# DAC.net
KiCad netlist of a schematic drawn in EAGLE
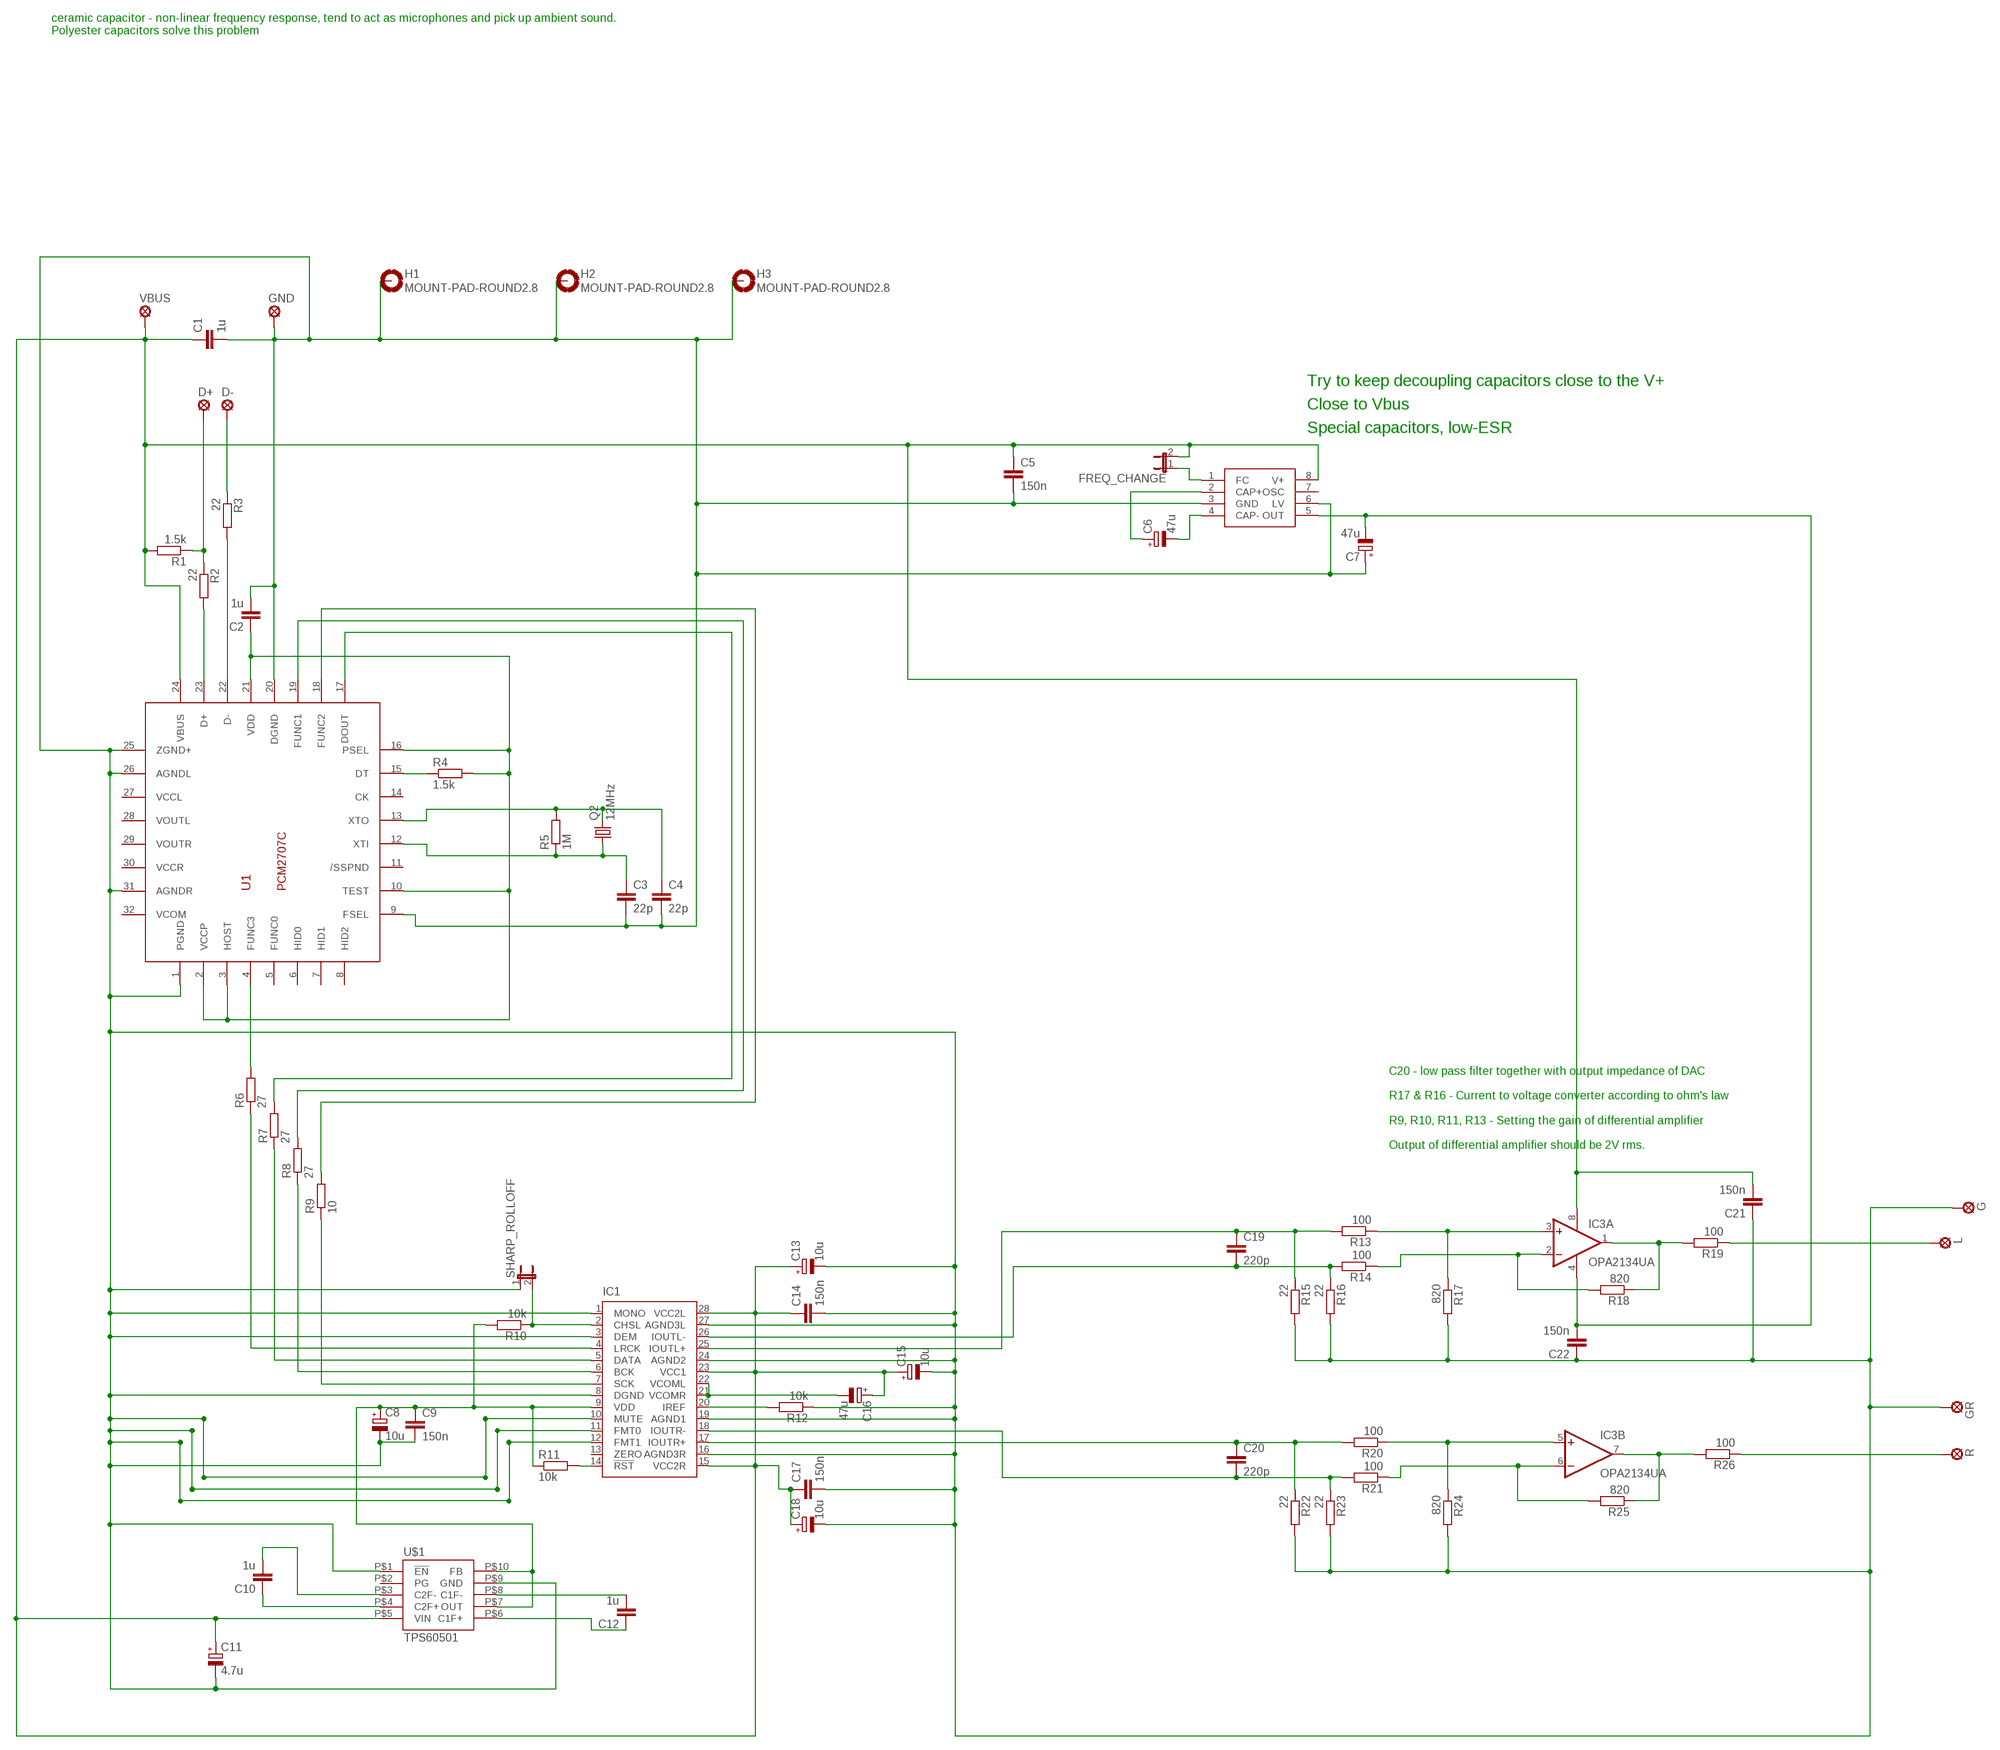
[diagram p0: schematic, sheet 1]

(export (version "E")
  (design (tool "Eeschema 10.0.6"))
  (components
    (comp (ref "C1")
      (value "1u")
      (footprint "eagle-import:C050-050X075")
      (libsource (lib "eagle-import") (part "C-EU050-050X075"))
    )
    (comp (ref "C2")
      (value "1u")
      (footprint "eagle-import:C050-050X075")
      (libsource (lib "eagle-import") (part "C-EU050-050X075"))
    )
    (comp (ref "C3")
      (value "22p")
      (footprint "eagle-import:C0603")
      (libsource (lib "eagle-import") (part "C-EUC0603"))
    )
    (comp (ref "C4")
      (value "22p")
      (footprint "eagle-import:C0603")
      (libsource (lib "eagle-import") (part "C-EUC0603"))
    )
    (comp (ref "C5")
      (value "150n")
      (footprint "eagle-import:C050-025X075")
      (libsource (lib "eagle-import") (part "C-EU050-025X075"))
    )
    (comp (ref "C6")
      (value "47u")
      (footprint "eagle-import:PANASONIC_D")
      (libsource (lib "eagle-import") (part "CPOL-EUD"))
    )
    (comp (ref "C7")
      (value "47u")
      (footprint "eagle-import:PANASONIC_D")
      (libsource (lib "eagle-import") (part "CPOL-EUD"))
    )
    (comp (ref "C8")
      (value "10u")
      (footprint "eagle-import:153CLV-0405")
      (libsource (lib "eagle-import") (part "CPOL-EU153CLV-0405"))
    )
    (comp (ref "C9")
      (value "150n")
      (footprint "eagle-import:C050-025X075")
      (libsource (lib "eagle-import") (part "C-EU050-025X075"))
    )
    (comp (ref "C10")
      (value "1u")
      (footprint "eagle-import:C050-050X075")
      (libsource (lib "eagle-import") (part "C-EU050-050X075"))
    )
    (comp (ref "C11")
      (value "4.7u")
      (footprint "eagle-import:E2-5")
      (libsource (lib "eagle-import") (part "CPOL-EUE2-5"))
    )
    (comp (ref "C12")
      (value "1u")
      (footprint "eagle-import:C050-050X075")
      (libsource (lib "eagle-import") (part "C-EU050-050X075"))
    )
    (comp (ref "C13")
      (value "10u")
      (footprint "eagle-import:E2-5")
      (libsource (lib "eagle-import") (part "CPOL-EUE2-5"))
    )
    (comp (ref "C14")
      (value "150n")
      (footprint "eagle-import:C050-025X075")
      (libsource (lib "eagle-import") (part "C-EU050-025X075"))
    )
    (comp (ref "C15")
      (value "10u")
      (footprint "eagle-import:E2-5")
      (libsource (lib "eagle-import") (part "CPOL-EUE2-5"))
    )
    (comp (ref "C16")
      (value "47u")
      (footprint "eagle-import:E2-5")
      (libsource (lib "eagle-import") (part "CPOL-EUE2-5"))
    )
    (comp (ref "C17")
      (value "150n")
      (footprint "eagle-import:C050-025X075")
      (libsource (lib "eagle-import") (part "C-EU050-025X075"))
    )
    (comp (ref "C18")
      (value "10u")
      (footprint "eagle-import:E2-5")
      (libsource (lib "eagle-import") (part "CPOL-EUE2-5"))
    )
    (comp (ref "C19")
      (value "220p")
      (footprint "eagle-import:C025-024X044")
      (libsource (lib "eagle-import") (part "C-EU025-024X044"))
    )
    (comp (ref "C20")
      (value "220p")
      (footprint "eagle-import:C025-024X044")
      (libsource (lib "eagle-import") (part "C-EU025-024X044"))
    )
    (comp (ref "C21")
      (value "150n")
      (footprint "eagle-import:C050-025X075")
      (libsource (lib "eagle-import") (part "C-EU050-025X075"))
    )
    (comp (ref "C22")
      (value "150n")
      (footprint "eagle-import:C050-025X075")
      (libsource (lib "eagle-import") (part "C-EU050-025X075"))
    )
    (comp (ref "D+")
      (value "LSP10")
      (footprint "eagle-import:LSP10")
      (libsource (lib "eagle-import") (part "LSP10"))
    )
    (comp (ref "D-")
      (value "LSP10")
      (footprint "eagle-import:LSP10")
      (libsource (lib "eagle-import") (part "LSP10"))
    )
    (comp (ref "FREQ_CHANGE")
      (value "JP1E")
      (footprint "eagle-import:JP1")
      (libsource (lib "eagle-import") (part "JP1E"))
    )
    (comp (ref "G")
      (value "LSP10")
      (footprint "eagle-import:LSP10")
      (libsource (lib "eagle-import") (part "LSP10"))
    )
    (comp (ref "GND")
      (value "LSP10")
      (footprint "eagle-import:LSP10")
      (libsource (lib "eagle-import") (part "LSP10"))
    )
    (comp (ref "GR")
      (value "LSP10")
      (footprint "eagle-import:LSP10")
      (libsource (lib "eagle-import") (part "LSP10"))
    )
    (comp (ref "H1")
      (value "MOUNT-PAD-ROUND2.8")
      (footprint "eagle-import:2,8-PAD")
      (libsource (lib "eagle-import") (part "MOUNT-PAD-ROUND2.8"))
    )
    (comp (ref "H2")
      (value "MOUNT-PAD-ROUND2.8")
      (footprint "eagle-import:2,8-PAD")
      (libsource (lib "eagle-import") (part "MOUNT-PAD-ROUND2.8"))
    )
    (comp (ref "H3")
      (value "MOUNT-PAD-ROUND2.8")
      (footprint "eagle-import:2,8-PAD")
      (libsource (lib "eagle-import") (part "MOUNT-PAD-ROUND2.8"))
    )
    (comp (ref "IC1")
      (value "PCM1794A")
      (footprint "eagle-import:SSOP28DB")
      (libsource (lib "eagle-import") (part "PCM1794A"))
    )
    (comp (ref "IC3")
      (value "OPA2134UA")
      (footprint "eagle-import:SO08")
      (libsource (lib "eagle-import") (part "OPA2UA134"))
    )
    (comp (ref "L")
      (value "LSP10")
      (footprint "eagle-import:LSP10")
      (libsource (lib "eagle-import") (part "LSP10"))
    )
    (comp (ref "Q2")
      (value "12MHz")
      (footprint "eagle-import:HC49_S")
      (libsource (lib "eagle-import") (part "CRYSTALHC49S"))
    )
    (comp (ref "R")
      (value "LSP10")
      (footprint "eagle-import:LSP10")
      (libsource (lib "eagle-import") (part "LSP10"))
    )
    (comp (ref "R1")
      (value "1.5k")
      (footprint "eagle-import:R0603")
      (libsource (lib "eagle-import") (part "R-EU_R0603"))
    )
    (comp (ref "R2")
      (value "22")
      (footprint "eagle-import:R0603")
      (libsource (lib "eagle-import") (part "R-EU_R0603"))
    )
    (comp (ref "R3")
      (value "22")
      (footprint "eagle-import:R0603")
      (libsource (lib "eagle-import") (part "R-EU_R0603"))
    )
    (comp (ref "R4")
      (value "1.5k")
      (footprint "eagle-import:R0603")
      (libsource (lib "eagle-import") (part "R-EU_R0603"))
    )
    (comp (ref "R5")
      (value "1M")
      (footprint "eagle-import:R0603")
      (libsource (lib "eagle-import") (part "R-EU_R0603"))
    )
    (comp (ref "R6")
      (value "27")
      (footprint "eagle-import:R0603")
      (libsource (lib "eagle-import") (part "R-EU_R0603"))
    )
    (comp (ref "R7")
      (value "27")
      (footprint "eagle-import:R0603")
      (libsource (lib "eagle-import") (part "R-EU_R0603"))
    )
    (comp (ref "R8")
      (value "27")
      (footprint "eagle-import:R0603")
      (libsource (lib "eagle-import") (part "R-EU_R0603"))
    )
    (comp (ref "R9")
      (value "10")
      (footprint "eagle-import:R0603")
      (libsource (lib "eagle-import") (part "R-EU_R0603"))
    )
    (comp (ref "R10")
      (value "10k")
      (footprint "eagle-import:R0603")
      (libsource (lib "eagle-import") (part "R-EU_R0603"))
    )
    (comp (ref "R11")
      (value "10k")
      (footprint "eagle-import:R0603")
      (libsource (lib "eagle-import") (part "R-EU_R0603"))
    )
    (comp (ref "R12")
      (value "10k")
      (footprint "eagle-import:0207_10")
      (libsource (lib "eagle-import") (part "R-EU_0207/10"))
    )
    (comp (ref "R13")
      (value "100")
      (footprint "eagle-import:0207_10")
      (libsource (lib "eagle-import") (part "R-EU_0207/10"))
    )
    (comp (ref "R14")
      (value "100")
      (footprint "eagle-import:0207_10")
      (libsource (lib "eagle-import") (part "R-EU_0207/10"))
    )
    (comp (ref "R15")
      (value "22")
      (footprint "eagle-import:0207_10")
      (libsource (lib "eagle-import") (part "R-EU_0207/10"))
    )
    (comp (ref "R16")
      (value "22")
      (footprint "eagle-import:0207_10")
      (libsource (lib "eagle-import") (part "R-EU_0207/10"))
    )
    (comp (ref "R17")
      (value "820")
      (footprint "eagle-import:0207_10")
      (libsource (lib "eagle-import") (part "R-EU_0207/10"))
    )
    (comp (ref "R18")
      (value "820")
      (footprint "eagle-import:0207_10")
      (libsource (lib "eagle-import") (part "R-EU_0207/10"))
    )
    (comp (ref "R19")
      (value "100")
      (footprint "eagle-import:0207_10")
      (libsource (lib "eagle-import") (part "R-EU_0207/10"))
    )
    (comp (ref "R20")
      (value "100")
      (footprint "eagle-import:0207_10")
      (libsource (lib "eagle-import") (part "R-EU_0207/10"))
    )
    (comp (ref "R21")
      (value "100")
      (footprint "eagle-import:0207_10")
      (libsource (lib "eagle-import") (part "R-EU_0207/10"))
    )
    (comp (ref "R22")
      (value "22")
      (footprint "eagle-import:0207_10")
      (libsource (lib "eagle-import") (part "R-EU_0207/10"))
    )
    (comp (ref "R23")
      (value "22")
      (footprint "eagle-import:0207_10")
      (libsource (lib "eagle-import") (part "R-EU_0207/10"))
    )
    (comp (ref "R24")
      (value "820")
      (footprint "eagle-import:0207_10")
      (libsource (lib "eagle-import") (part "R-EU_0207/10"))
    )
    (comp (ref "R25")
      (value "820")
      (footprint "eagle-import:0207_10")
      (libsource (lib "eagle-import") (part "R-EU_0207/10"))
    )
    (comp (ref "R26")
      (value "100")
      (footprint "eagle-import:0207_10")
      (libsource (lib "eagle-import") (part "R-EU_0207/10"))
    )
    (comp (ref "SHARP_ROLLOFF")
      (value "JP1E")
      (footprint "eagle-import:JP1")
      (libsource (lib "eagle-import") (part "JP1E"))
    )
    (comp (ref "U$1")
      (value "TPS60501")
      (footprint "eagle-import:VSSOP10")
      (libsource (lib "eagle-import") (part "TPS60501"))
    )
    (comp (ref "U$2")
      (value "LM2662")
      (footprint "eagle-import:SOIC8")
      (libsource (lib "eagle-import") (part "LM2662"))
    )
    (comp (ref "U1")
      (value "PCM2707C")
      (footprint "eagle-import:32TQFP_PCM2707C")
      (libsource (lib "eagle-import") (part "PCM2707C_TQFP32{dblquote}"))
    )
    (comp (ref "VBUS")
      (value "LSP10")
      (footprint "eagle-import:LSP10")
      (libsource (lib "eagle-import") (part "LSP10"))
    )
  )
  (nets
    (net (code "1") (name "Net-(D+-PadMP)") (class "Default")
      (node (ref "D+") (pin "MP") (pinfunction "MP_MP") (pintype "passive"))
      (node (ref "R1") (pin "1") (pinfunction "1_1") (pintype "passive"))
      (node (ref "R2") (pin "1") (pinfunction "1_1") (pintype "passive"))
    )
    (net (code "2") (name "Net-(D--PadMP)") (class "Default")
      (node (ref "D-") (pin "MP") (pinfunction "MP_MP") (pintype "passive"))
      (node (ref "R3") (pin "1") (pinfunction "1_1") (pintype "passive"))
    )
    (net (code "3") (name "Net-(H1-MOUNT)") (class "Default")
      (node (ref "C1") (pin "2") (pinfunction "2_2") (pintype "passive"))
      (node (ref "C11") (pin "-") (pinfunction "-_-") (pintype "passive"))
      (node (ref "C13") (pin "-") (pinfunction "-_-") (pintype "passive"))
      (node (ref "C14") (pin "2") (pinfunction "2_2") (pintype "passive"))
      (node (ref "C15") (pin "-") (pinfunction "-_-") (pintype "passive"))
      (node (ref "C17") (pin "2") (pinfunction "2_2") (pintype "passive"))
      (node (ref "C18") (pin "-") (pinfunction "-_-") (pintype "passive"))
      (node (ref "C2") (pin "2") (pinfunction "2_2") (pintype "passive"))
      (node (ref "C21") (pin "1") (pinfunction "1_1") (pintype "passive"))
      (node (ref "C22") (pin "1") (pinfunction "1_1") (pintype "passive"))
      (node (ref "C3") (pin "2") (pinfunction "2_2") (pintype "passive"))
      (node (ref "C4") (pin "2") (pinfunction "2_2") (pintype "passive"))
      (node (ref "C5") (pin "2") (pinfunction "2_2") (pintype "passive"))
      (node (ref "C7") (pin "+") (pinfunction "+_+") (pintype "passive"))
      (node (ref "C8") (pin "-") (pinfunction "-_-") (pintype "passive"))
      (node (ref "C9") (pin "2") (pinfunction "2_2") (pintype "passive"))
      (node (ref "G") (pin "MP") (pinfunction "MP_MP") (pintype "passive"))
      (node (ref "GND") (pin "MP") (pinfunction "MP_MP") (pintype "passive"))
      (node (ref "GR") (pin "MP") (pinfunction "MP_MP") (pintype "passive"))
      (node (ref "H1") (pin "B2,8") (pinfunction "MOUNT_B2,8") (pintype "passive"))
      (node (ref "H2") (pin "B2,8") (pinfunction "MOUNT_B2,8") (pintype "passive"))
      (node (ref "H3") (pin "B2,8") (pinfunction "MOUNT_B2,8") (pintype "passive"))
      (node (ref "IC1") (pin "1") (pinfunction "MONO_1") (pintype "input"))
      (node (ref "IC1") (pin "10") (pinfunction "MUTE_10") (pintype "input"))
      (node (ref "IC1") (pin "11") (pinfunction "FMT0_11") (pintype "input"))
      (node (ref "IC1") (pin "12") (pinfunction "FMT1_12") (pintype "input"))
      (node (ref "IC1") (pin "16") (pinfunction "AGND3R_16") (pintype "power_in"))
      (node (ref "IC1") (pin "19") (pinfunction "AGND1_19") (pintype "power_in"))
      (node (ref "IC1") (pin "24") (pinfunction "AGND2_24") (pintype "power_in"))
      (node (ref "IC1") (pin "27") (pinfunction "AGND3L_27") (pintype "power_in"))
      (node (ref "IC1") (pin "3") (pinfunction "DEM_3") (pintype "input"))
      (node (ref "IC1") (pin "8") (pinfunction "DGND_8") (pintype "power_in"))
      (node (ref "R12") (pin "1") (pinfunction "1_1") (pintype "passive"))
      (node (ref "R15") (pin "2") (pinfunction "2_2") (pintype "passive"))
      (node (ref "R16") (pin "2") (pinfunction "2_2") (pintype "passive"))
      (node (ref "R17") (pin "2") (pinfunction "2_2") (pintype "passive"))
      (node (ref "R22") (pin "2") (pinfunction "2_2") (pintype "passive"))
      (node (ref "R23") (pin "2") (pinfunction "2_2") (pintype "passive"))
      (node (ref "R24") (pin "2") (pinfunction "2_2") (pintype "passive"))
      (node (ref "SHARP_ROLLOFF") (pin "1") (pinfunction "1_1") (pintype "passive"))
      (node (ref "U$1") (pin "P$1") (pinfunction "~{EN}_P$1") (pintype "bidirectional"))
      (node (ref "U$1") (pin "P$9") (pinfunction "GND_P$9") (pintype "bidirectional"))
      (node (ref "U$2") (pin "3") (pinfunction "GND_3") (pintype "bidirectional"))
      (node (ref "U$2") (pin "6") (pinfunction "LV_6") (pintype "bidirectional"))
      (node (ref "U1") (pin "1") (pinfunction "PGND_1") (pintype "bidirectional"))
      (node (ref "U1") (pin "20") (pinfunction "DGND_20") (pintype "bidirectional"))
      (node (ref "U1") (pin "25") (pinfunction "ZGND+_25") (pintype "bidirectional"))
      (node (ref "U1") (pin "26") (pinfunction "AGNDL_26") (pintype "bidirectional"))
      (node (ref "U1") (pin "31") (pinfunction "AGNDR_31") (pintype "bidirectional"))
      (node (ref "U1") (pin "9") (pinfunction "FSEL_9") (pintype "bidirectional"))
    )
    (net (code "4") (name "Net-(IC1-BCK)") (class "Default")
      (node (ref "IC1") (pin "6") (pinfunction "BCK_6") (pintype "input"))
      (node (ref "R8") (pin "1") (pinfunction "1_1") (pintype "passive"))
    )
    (net (code "5") (name "Net-(IC1-CHSL)") (class "Default")
      (node (ref "IC1") (pin "2") (pinfunction "CHSL_2") (pintype "input"))
      (node (ref "R10") (pin "1") (pinfunction "1_1") (pintype "passive"))
      (node (ref "SHARP_ROLLOFF") (pin "2") (pinfunction "2_2") (pintype "passive"))
    )
    (net (code "6") (name "Net-(IC1-DATA)") (class "Default")
      (node (ref "IC1") (pin "5") (pinfunction "DATA_5") (pintype "input"))
      (node (ref "R7") (pin "1") (pinfunction "1_1") (pintype "passive"))
    )
    (net (code "7") (name "Net-(IC1-IOUTL+)") (class "Default")
      (node (ref "C19") (pin "1") (pinfunction "1_1") (pintype "passive"))
      (node (ref "IC1") (pin "25") (pinfunction "IOUTL+_25") (pintype "output"))
      (node (ref "R13") (pin "2") (pinfunction "2_2") (pintype "passive"))
      (node (ref "R15") (pin "1") (pinfunction "1_1") (pintype "passive"))
    )
    (net (code "8") (name "Net-(IC1-IOUTL-)") (class "Default")
      (node (ref "C19") (pin "2") (pinfunction "2_2") (pintype "passive"))
      (node (ref "IC1") (pin "26") (pinfunction "IOUTL-_26") (pintype "output"))
      (node (ref "R14") (pin "2") (pinfunction "2_2") (pintype "passive"))
      (node (ref "R16") (pin "1") (pinfunction "1_1") (pintype "passive"))
    )
    (net (code "9") (name "Net-(IC1-IOUTR+)") (class "Default")
      (node (ref "C20") (pin "1") (pinfunction "1_1") (pintype "passive"))
      (node (ref "IC1") (pin "17") (pinfunction "IOUTR+_17") (pintype "output"))
      (node (ref "R20") (pin "2") (pinfunction "2_2") (pintype "passive"))
      (node (ref "R22") (pin "1") (pinfunction "1_1") (pintype "passive"))
    )
    (net (code "10") (name "Net-(IC1-IOUTR-)") (class "Default")
      (node (ref "C20") (pin "2") (pinfunction "2_2") (pintype "passive"))
      (node (ref "IC1") (pin "18") (pinfunction "IOUTR-_18") (pintype "output"))
      (node (ref "R21") (pin "2") (pinfunction "2_2") (pintype "passive"))
      (node (ref "R23") (pin "1") (pinfunction "1_1") (pintype "passive"))
    )
    (net (code "11") (name "Net-(IC1-IREF)") (class "Default")
      (node (ref "IC1") (pin "20") (pinfunction "IREF_20") (pintype "power_in"))
      (node (ref "R12") (pin "2") (pinfunction "2_2") (pintype "passive"))
    )
    (net (code "12") (name "Net-(IC1-LRCK)") (class "Default")
      (node (ref "IC1") (pin "4") (pinfunction "LRCK_4") (pintype "input"))
      (node (ref "R6") (pin "1") (pinfunction "1_1") (pintype "passive"))
    )
    (net (code "13") (name "Net-(IC1-SCK)") (class "Default")
      (node (ref "IC1") (pin "7") (pinfunction "SCK_7") (pintype "input"))
      (node (ref "R9") (pin "1") (pinfunction "1_1") (pintype "passive"))
    )
    (net (code "14") (name "Net-(IC1-VCC1)") (class "Default")
      (node (ref "C1") (pin "1") (pinfunction "1_1") (pintype "passive"))
      (node (ref "C11") (pin "+") (pinfunction "+_+") (pintype "passive"))
      (node (ref "C13") (pin "+") (pinfunction "+_+") (pintype "passive"))
      (node (ref "C14") (pin "1") (pinfunction "1_1") (pintype "passive"))
      (node (ref "C15") (pin "+") (pinfunction "+_+") (pintype "passive"))
      (node (ref "C16") (pin "+") (pinfunction "+_+") (pintype "passive"))
      (node (ref "C17") (pin "1") (pinfunction "1_1") (pintype "passive"))
      (node (ref "C18") (pin "+") (pinfunction "+_+") (pintype "passive"))
      (node (ref "C21") (pin "2") (pinfunction "2_2") (pintype "passive"))
      (node (ref "C5") (pin "1") (pinfunction "1_1") (pintype "passive"))
      (node (ref "FREQ_CHANGE") (pin "2") (pinfunction "2_2") (pintype "passive"))
      (node (ref "IC1") (pin "15") (pinfunction "VCC2R_15") (pintype "power_in"))
      (node (ref "IC1") (pin "23") (pinfunction "VCC1_23") (pintype "power_in"))
      (node (ref "IC1") (pin "28") (pinfunction "VCC2L_28") (pintype "power_in"))
      (node (ref "IC3") (pin "8") (pinfunction "V+_8") (pintype "power_in"))
      (node (ref "R1") (pin "2") (pinfunction "2_2") (pintype "passive"))
      (node (ref "U$1") (pin "P$5") (pinfunction "VIN_P$5") (pintype "bidirectional"))
      (node (ref "U$2") (pin "8") (pinfunction "V+_8") (pintype "bidirectional"))
      (node (ref "U1") (pin "24") (pinfunction "VBUS_24") (pintype "bidirectional"))
      (node (ref "VBUS") (pin "MP") (pinfunction "MP_MP") (pintype "passive"))
    )
    (net (code "15") (name "Net-(IC1-VCOML)") (class "Default")
      (node (ref "C16") (pin "-") (pinfunction "-_-") (pintype "passive"))
      (node (ref "IC1") (pin "21") (pinfunction "VCOMR_21") (pintype "power_in"))
      (node (ref "IC1") (pin "22") (pinfunction "VCOML_22") (pintype "power_in"))
    )
    (net (code "16") (name "Net-(IC1-VDD)") (class "Default")
      (node (ref "C8") (pin "+") (pinfunction "+_+") (pintype "passive"))
      (node (ref "C9") (pin "1") (pinfunction "1_1") (pintype "passive"))
      (node (ref "IC1") (pin "9") (pinfunction "VDD_9") (pintype "power_in"))
      (node (ref "R10") (pin "2") (pinfunction "2_2") (pintype "passive"))
      (node (ref "R11") (pin "1") (pinfunction "1_1") (pintype "passive"))
      (node (ref "U$1") (pin "P$10") (pinfunction "FB_P$10") (pintype "bidirectional"))
      (node (ref "U$1") (pin "P$7") (pinfunction "OUT_P$7") (pintype "bidirectional"))
    )
    (net (code "17") (name "Net-(IC1-~{RST})") (class "Default")
      (node (ref "IC1") (pin "14") (pinfunction "~{RST}_14") (pintype "input"))
      (node (ref "R11") (pin "2") (pinfunction "2_2") (pintype "passive"))
    )
    (net (code "18") (name "Net-(IC3A-+IN)") (class "Default")
      (node (ref "IC3") (pin "3") (pinfunction "+IN_3") (pintype "input"))
      (node (ref "R13") (pin "1") (pinfunction "1_1") (pintype "passive"))
      (node (ref "R17") (pin "1") (pinfunction "1_1") (pintype "passive"))
    )
    (net (code "19") (name "Net-(IC3A--IN)") (class "Default")
      (node (ref "IC3") (pin "2") (pinfunction "-IN_2") (pintype "input"))
      (node (ref "R14") (pin "1") (pinfunction "1_1") (pintype "passive"))
      (node (ref "R18") (pin "2") (pinfunction "2_2") (pintype "passive"))
    )
    (net (code "20") (name "Net-(IC3A-OUT)") (class "Default")
      (node (ref "IC3") (pin "1") (pinfunction "OUT_1") (pintype "output"))
      (node (ref "R18") (pin "1") (pinfunction "1_1") (pintype "passive"))
      (node (ref "R19") (pin "2") (pinfunction "2_2") (pintype "passive"))
    )
    (net (code "21") (name "Net-(IC3A-V-)") (class "Default")
      (node (ref "C22") (pin "2") (pinfunction "2_2") (pintype "passive"))
      (node (ref "C7") (pin "-") (pinfunction "-_-") (pintype "passive"))
      (node (ref "IC3") (pin "4") (pinfunction "V-_4") (pintype "power_in"))
      (node (ref "U$2") (pin "5") (pinfunction "OUT_5") (pintype "bidirectional"))
    )
    (net (code "22") (name "Net-(IC3B-+IN)") (class "Default")
      (node (ref "IC3") (pin "5") (pinfunction "+IN_5") (pintype "input"))
      (node (ref "R20") (pin "1") (pinfunction "1_1") (pintype "passive"))
      (node (ref "R24") (pin "1") (pinfunction "1_1") (pintype "passive"))
    )
    (net (code "23") (name "Net-(IC3B--IN)") (class "Default")
      (node (ref "IC3") (pin "6") (pinfunction "-IN_6") (pintype "input"))
      (node (ref "R21") (pin "1") (pinfunction "1_1") (pintype "passive"))
      (node (ref "R25") (pin "2") (pinfunction "2_2") (pintype "passive"))
    )
    (net (code "24") (name "Net-(IC3B-OUT)") (class "Default")
      (node (ref "IC3") (pin "7") (pinfunction "OUT_7") (pintype "output"))
      (node (ref "R25") (pin "1") (pinfunction "1_1") (pintype "passive"))
      (node (ref "R26") (pin "2") (pinfunction "2_2") (pintype "passive"))
    )
    (net (code "25") (name "Net-(L-PadMP)") (class "Default")
      (node (ref "L") (pin "MP") (pinfunction "MP_MP") (pintype "passive"))
      (node (ref "R19") (pin "1") (pinfunction "1_1") (pintype "passive"))
    )
    (net (code "26") (name "Net-(R-PadMP)") (class "Default")
      (node (ref "R") (pin "MP") (pinfunction "MP_MP") (pintype "passive"))
      (node (ref "R26") (pin "1") (pinfunction "1_1") (pintype "passive"))
    )
    (net (code "27") (name "Net-(U$1-C1F+)") (class "Default")
      (node (ref "C12") (pin "1") (pinfunction "1_1") (pintype "passive"))
      (node (ref "U$1") (pin "P$6") (pinfunction "C1F+_P$6") (pintype "bidirectional"))
    )
    (net (code "28") (name "Net-(U$1-C1F-)") (class "Default")
      (node (ref "C12") (pin "2") (pinfunction "2_2") (pintype "passive"))
      (node (ref "U$1") (pin "P$8") (pinfunction "C1F-_P$8") (pintype "bidirectional"))
    )
    (net (code "29") (name "Net-(U$1-C2F+)") (class "Default")
      (node (ref "C10") (pin "1") (pinfunction "1_1") (pintype "passive"))
      (node (ref "U$1") (pin "P$4") (pinfunction "C2F+_P$4") (pintype "bidirectional"))
    )
    (net (code "30") (name "Net-(U$1-C2F-)") (class "Default")
      (node (ref "C10") (pin "2") (pinfunction "2_2") (pintype "passive"))
      (node (ref "U$1") (pin "P$3") (pinfunction "C2F-_P$3") (pintype "bidirectional"))
    )
    (net (code "31") (name "Net-(U$2-CAP+)") (class "Default")
      (node (ref "C6") (pin "+") (pinfunction "+_+") (pintype "passive"))
      (node (ref "U$2") (pin "2") (pinfunction "CAP+_2") (pintype "bidirectional"))
    )
    (net (code "32") (name "Net-(U$2-CAP-)") (class "Default")
      (node (ref "C6") (pin "-") (pinfunction "-_-") (pintype "passive"))
      (node (ref "U$2") (pin "4") (pinfunction "CAP-_4") (pintype "bidirectional"))
    )
    (net (code "33") (name "Net-(U$2-FC)") (class "Default")
      (node (ref "FREQ_CHANGE") (pin "1") (pinfunction "1_1") (pintype "passive"))
      (node (ref "U$2") (pin "1") (pinfunction "FC_1") (pintype "bidirectional"))
    )
    (net (code "34") (name "Net-(U1-D+)") (class "Default")
      (node (ref "R2") (pin "2") (pinfunction "2_2") (pintype "passive"))
      (node (ref "U1") (pin "23") (pinfunction "D+_23") (pintype "bidirectional"))
    )
    (net (code "35") (name "Net-(U1-D-)") (class "Default")
      (node (ref "R3") (pin "2") (pinfunction "2_2") (pintype "passive"))
      (node (ref "U1") (pin "22") (pinfunction "D-_22") (pintype "bidirectional"))
    )
    (net (code "36") (name "Net-(U1-DOUT)") (class "Default")
      (node (ref "R7") (pin "2") (pinfunction "2_2") (pintype "passive"))
      (node (ref "U1") (pin "17") (pinfunction "DOUT_17") (pintype "bidirectional"))
    )
    (net (code "37") (name "Net-(U1-DT)") (class "Default")
      (node (ref "R4") (pin "1") (pinfunction "1_1") (pintype "passive"))
      (node (ref "U1") (pin "15") (pinfunction "DT_15") (pintype "bidirectional"))
    )
    (net (code "38") (name "Net-(U1-FUNC1)") (class "Default")
      (node (ref "R8") (pin "2") (pinfunction "2_2") (pintype "passive"))
      (node (ref "U1") (pin "19") (pinfunction "FUNC1_19") (pintype "bidirectional"))
    )
    (net (code "39") (name "Net-(U1-FUNC2)") (class "Default")
      (node (ref "R9") (pin "2") (pinfunction "2_2") (pintype "passive"))
      (node (ref "U1") (pin "18") (pinfunction "FUNC2_18") (pintype "bidirectional"))
    )
    (net (code "40") (name "Net-(U1-FUNC3)") (class "Default")
      (node (ref "R6") (pin "2") (pinfunction "2_2") (pintype "passive"))
      (node (ref "U1") (pin "4") (pinfunction "FUNC3_4") (pintype "bidirectional"))
    )
    (net (code "41") (name "Net-(U1-HOST)") (class "Default")
      (node (ref "C2") (pin "1") (pinfunction "1_1") (pintype "passive"))
      (node (ref "R4") (pin "2") (pinfunction "2_2") (pintype "passive"))
      (node (ref "U1") (pin "10") (pinfunction "TEST_10") (pintype "bidirectional"))
      (node (ref "U1") (pin "16") (pinfunction "PSEL_16") (pintype "bidirectional"))
      (node (ref "U1") (pin "2") (pinfunction "VCCP_2") (pintype "bidirectional"))
      (node (ref "U1") (pin "21") (pinfunction "VDD_21") (pintype "bidirectional"))
      (node (ref "U1") (pin "3") (pinfunction "HOST_3") (pintype "bidirectional"))
    )
    (net (code "42") (name "Net-(U1-XTI)") (class "Default")
      (node (ref "C3") (pin "1") (pinfunction "1_1") (pintype "passive"))
      (node (ref "Q2") (pin "1") (pinfunction "1_1") (pintype "passive"))
      (node (ref "R5") (pin "1") (pinfunction "1_1") (pintype "passive"))
      (node (ref "U1") (pin "12") (pinfunction "XTI_12") (pintype "bidirectional"))
    )
    (net (code "43") (name "Net-(U1-XTO)") (class "Default")
      (node (ref "C4") (pin "1") (pinfunction "1_1") (pintype "passive"))
      (node (ref "Q2") (pin "2") (pinfunction "2_2") (pintype "passive"))
      (node (ref "R5") (pin "2") (pinfunction "2_2") (pintype "passive"))
      (node (ref "U1") (pin "13") (pinfunction "XTO_13") (pintype "bidirectional"))
    )
    (net (code "44") (name "unconnected-(IC1-ZERO-Pad13)") (class "Default")
      (node (ref "IC1") (pin "13") (pinfunction "ZERO_13") (pintype "output"))
    )
    (net (code "45") (name "unconnected-(U$1-PG-PadP$2)") (class "Default")
      (node (ref "U$1") (pin "P$2") (pinfunction "PG_P$2") (pintype "bidirectional"))
    )
    (net (code "46") (name "unconnected-(U$2-OSC-Pad7)") (class "Default")
      (node (ref "U$2") (pin "7") (pinfunction "OSC_7") (pintype "bidirectional"))
    )
    (net (code "47") (name "unconnected-(U1-CK-Pad14)") (class "Default")
      (node (ref "U1") (pin "14") (pinfunction "CK_14") (pintype "bidirectional"))
    )
    (net (code "48") (name "unconnected-(U1-FUNC0-Pad5)") (class "Default")
      (node (ref "U1") (pin "5") (pinfunction "FUNC0_5") (pintype "bidirectional"))
    )
    (net (code "49") (name "unconnected-(U1-HID0-Pad6)") (class "Default")
      (node (ref "U1") (pin "6") (pinfunction "HID0_6") (pintype "bidirectional"))
    )
    (net (code "50") (name "unconnected-(U1-HID1-Pad7)") (class "Default")
      (node (ref "U1") (pin "7") (pinfunction "HID1_7") (pintype "bidirectional"))
    )
    (net (code "51") (name "unconnected-(U1-HID2-Pad8)") (class "Default")
      (node (ref "U1") (pin "8") (pinfunction "HID2_8") (pintype "bidirectional"))
    )
    (net (code "52") (name "unconnected-(U1-VCCL-Pad27)") (class "Default")
      (node (ref "U1") (pin "27") (pinfunction "VCCL_27") (pintype "bidirectional"))
    )
    (net (code "53") (name "unconnected-(U1-VCCR-Pad30)") (class "Default")
      (node (ref "U1") (pin "30") (pinfunction "VCCR_30") (pintype "bidirectional"))
    )
    (net (code "54") (name "unconnected-(U1-VCOM-Pad32)") (class "Default")
      (node (ref "U1") (pin "32") (pinfunction "VCOM_32") (pintype "bidirectional"))
    )
    (net (code "55") (name "unconnected-(U1-VOUTL-Pad28)") (class "Default")
      (node (ref "U1") (pin "28") (pinfunction "VOUTL_28") (pintype "bidirectional"))
    )
    (net (code "56") (name "unconnected-(U1-VOUTR-Pad29)") (class "Default")
      (node (ref "U1") (pin "29") (pinfunction "VOUTR_29") (pintype "bidirectional"))
    )
    (net (code "57") (name "unconnected-(U1-{slash}SSPND-Pad11)") (class "Default")
      (node (ref "U1") (pin "11") (pinfunction "/SSPND_11") (pintype "bidirectional"))
    )
  )
)
